# ATTINY85ZIF.net
KiCad netlist of a schematic drawn in EAGLE
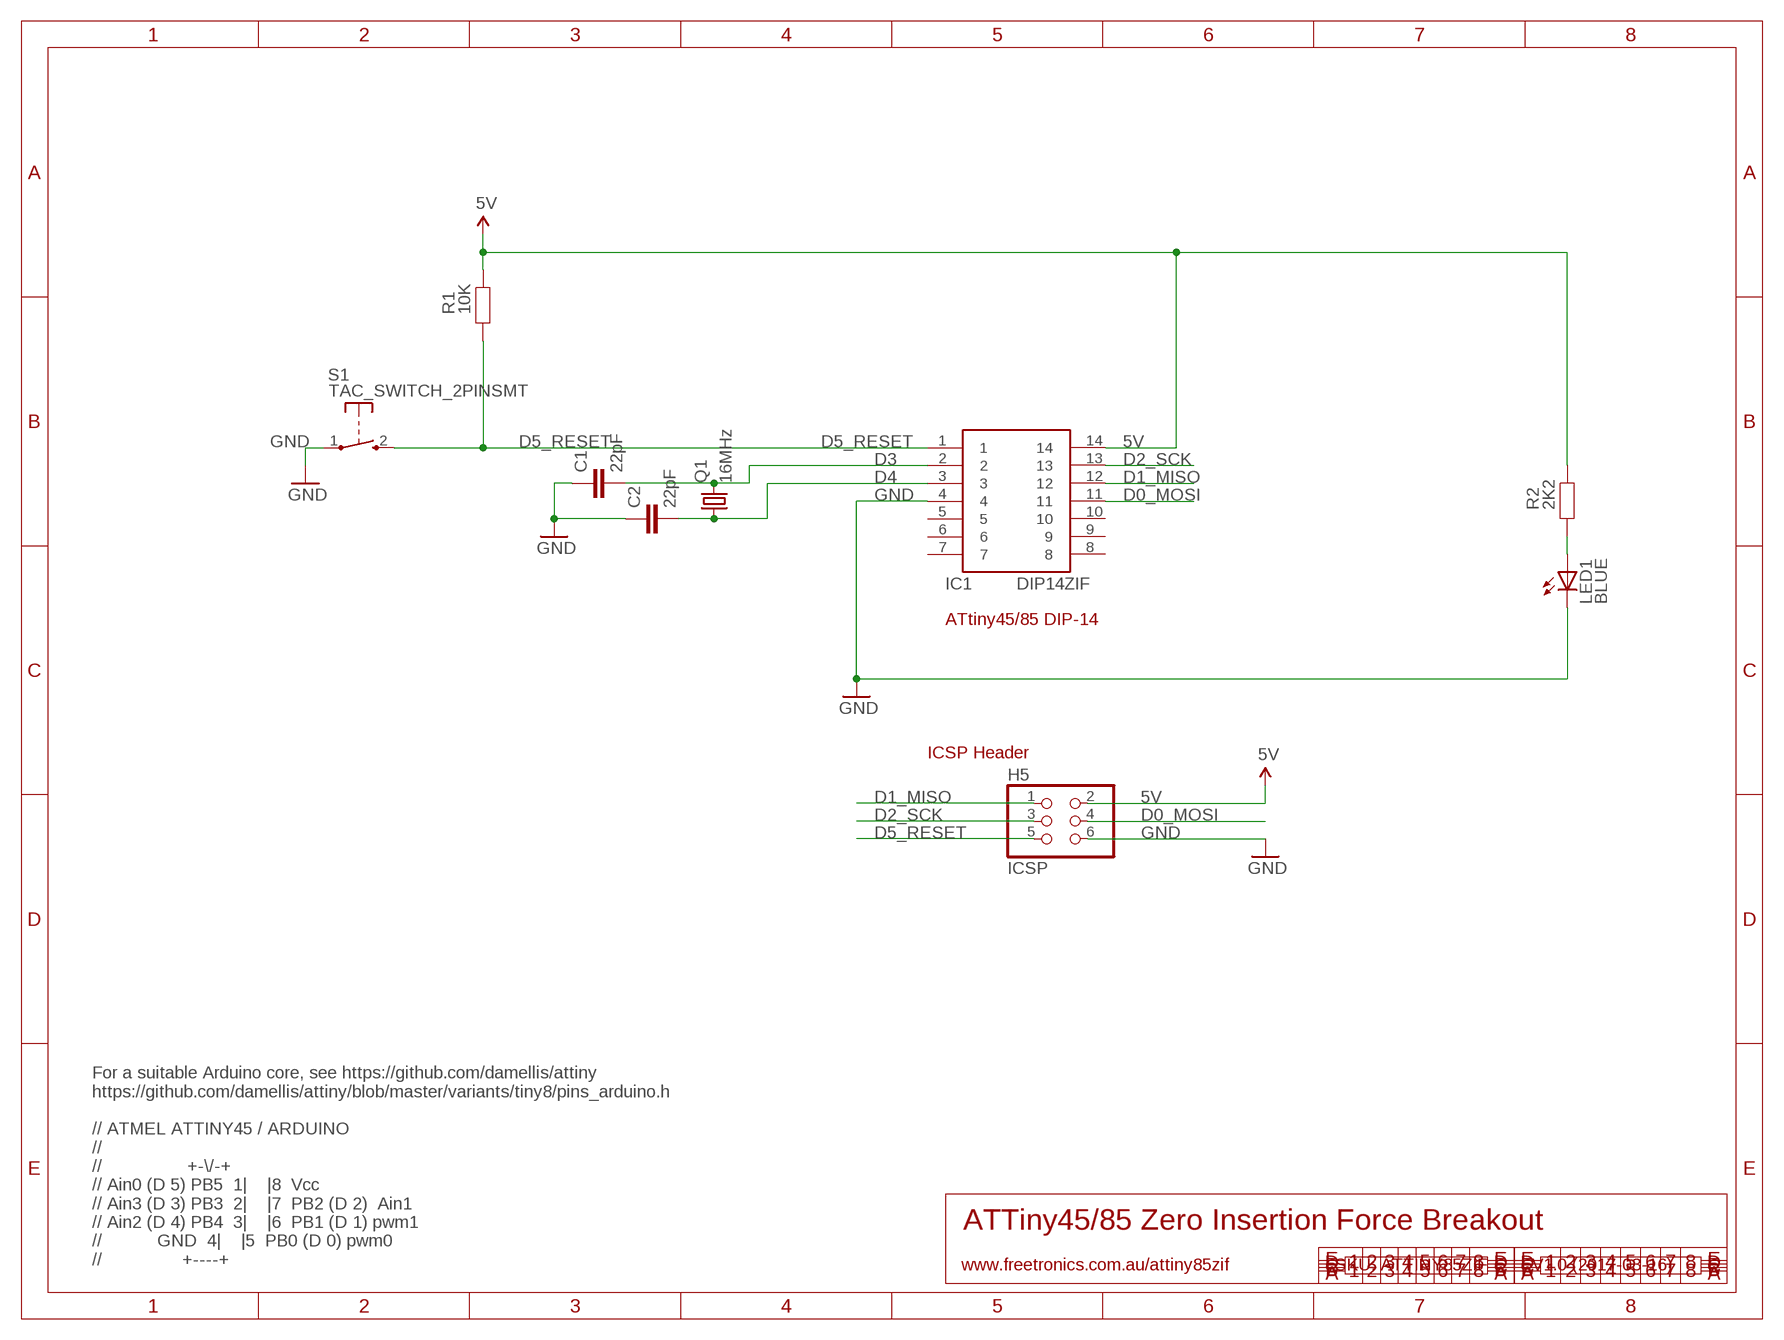
[diagram p0: schematic, sheet 1]

(export (version "E")
  (design (tool "Eeschema 10.0.6"))
  (components
    (comp (ref "C1")
      (value "22pF")
      (footprint "eagle-import:0603")
      (libsource (lib "eagle-import") (part "CAP0603"))
    )
    (comp (ref "C2")
      (value "22pF")
      (footprint "eagle-import:0603")
      (libsource (lib "eagle-import") (part "CAP0603"))
    )
    (comp (ref "H5")
      (value "ICSP")
      (footprint "eagle-import:2X03")
      (libsource (lib "eagle-import") (part "PINHD-2X3"))
    )
    (comp (ref "IC1")
      (value "DIP14ZIF")
      (footprint "eagle-import:DIL14-3-ZIF")
      (libsource (lib "eagle-import") (part "DIP14ZIF"))
    )
    (comp (ref "LED1")
      (value "BLUE")
      (footprint "eagle-import:LED-0603")
      (libsource (lib "eagle-import") (part "LED0603"))
    )
    (comp (ref "Q1")
      (value "16MHz")
      (footprint "eagle-import:HC49US")
      (libsource (lib "eagle-import") (part "CRYSTALHC49US"))
    )
    (comp (ref "R1")
      (value "10K")
      (footprint "eagle-import:0603")
      (libsource (lib "eagle-import") (part "RESISTOR0603"))
    )
    (comp (ref "R2")
      (value "2K2")
      (footprint "eagle-import:0603")
      (libsource (lib "eagle-import") (part "RESISTOR0603"))
    )
    (comp (ref "S1")
      (value "TAC_SWITCH_2PINSMT")
      (footprint "eagle-import:TACTILE_SWITCH_SMD_2PIN_TINY")
      (libsource (lib "eagle-import") (part "TAC_SWITCH_2PINSMT"))
    )
  )
  (nets
    (net (code "1") (name "/D0_MOSI") (class "Default")
      (node (ref "H5") (pin "4") (pinfunction "4_4") (pintype "passive"))
      (node (ref "IC1") (pin "11") (pinfunction "11_11") (pintype "bidirectional"))
    )
    (net (code "2") (name "/D1_MISO") (class "Default")
      (node (ref "H5") (pin "1") (pinfunction "1_1") (pintype "passive"))
      (node (ref "IC1") (pin "12") (pinfunction "12_12") (pintype "bidirectional"))
    )
    (net (code "3") (name "/D2_SCK") (class "Default")
      (node (ref "H5") (pin "3") (pinfunction "3_3") (pintype "passive"))
      (node (ref "IC1") (pin "13") (pinfunction "13_13") (pintype "bidirectional"))
    )
    (net (code "4") (name "/D3") (class "Default")
      (node (ref "C1") (pin "2") (pinfunction "2_2") (pintype "passive"))
      (node (ref "IC1") (pin "2") (pinfunction "2_2") (pintype "bidirectional"))
      (node (ref "Q1") (pin "2") (pinfunction "2_2") (pintype "passive"))
    )
    (net (code "5") (name "/D4") (class "Default")
      (node (ref "C2") (pin "2") (pinfunction "2_2") (pintype "passive"))
      (node (ref "IC1") (pin "3") (pinfunction "3_3") (pintype "bidirectional"))
      (node (ref "Q1") (pin "1") (pinfunction "1_1") (pintype "passive"))
    )
    (net (code "6") (name "/D5_RESET") (class "Default")
      (node (ref "H5") (pin "5") (pinfunction "5_5") (pintype "passive"))
      (node (ref "IC1") (pin "1") (pinfunction "1_1") (pintype "bidirectional"))
      (node (ref "R1") (pin "1") (pinfunction "1_1") (pintype "passive"))
      (node (ref "S1") (pin "2") (pinfunction "S_2") (pintype "passive"))
    )
    (net (code "7") (name "5V") (class "Default")
      (node (ref "H5") (pin "2") (pinfunction "2_2") (pintype "passive"))
      (node (ref "IC1") (pin "14") (pinfunction "14_14") (pintype "bidirectional"))
      (node (ref "R1") (pin "2") (pinfunction "2_2") (pintype "passive"))
      (node (ref "R2") (pin "2") (pinfunction "2_2") (pintype "passive"))
    )
    (net (code "8") (name "GND") (class "Default")
      (node (ref "C1") (pin "1") (pinfunction "1_1") (pintype "passive"))
      (node (ref "C2") (pin "1") (pinfunction "1_1") (pintype "passive"))
      (node (ref "H5") (pin "6") (pinfunction "6_6") (pintype "passive"))
      (node (ref "IC1") (pin "4") (pinfunction "4_4") (pintype "bidirectional"))
      (node (ref "LED1") (pin "C") (pinfunction "C_C") (pintype "passive"))
      (node (ref "S1") (pin "1") (pinfunction "P_1") (pintype "passive"))
    )
    (net (code "9") (name "Net-(LED1-PadA)") (class "Default")
      (node (ref "LED1") (pin "A") (pinfunction "A_A") (pintype "passive"))
      (node (ref "R2") (pin "1") (pinfunction "1_1") (pintype "passive"))
    )
    (net (code "10") (name "unconnected-(IC1-Pad5)") (class "Default")
      (node (ref "IC1") (pin "5") (pinfunction "5_5") (pintype "bidirectional"))
    )
    (net (code "11") (name "unconnected-(IC1-Pad6)") (class "Default")
      (node (ref "IC1") (pin "6") (pinfunction "6_6") (pintype "bidirectional"))
    )
    (net (code "12") (name "unconnected-(IC1-Pad7)") (class "Default")
      (node (ref "IC1") (pin "7") (pinfunction "7_7") (pintype "bidirectional"))
    )
    (net (code "13") (name "unconnected-(IC1-Pad8)") (class "Default")
      (node (ref "IC1") (pin "8") (pinfunction "8_8") (pintype "bidirectional"))
    )
    (net (code "14") (name "unconnected-(IC1-Pad9)") (class "Default")
      (node (ref "IC1") (pin "9") (pinfunction "9_9") (pintype "bidirectional"))
    )
    (net (code "15") (name "unconnected-(IC1-Pad10)") (class "Default")
      (node (ref "IC1") (pin "10") (pinfunction "10_10") (pintype "bidirectional"))
    )
  )
)
